# SD1-37_Rev1.net
KiCad netlist of a schematic drawn in EAGLE
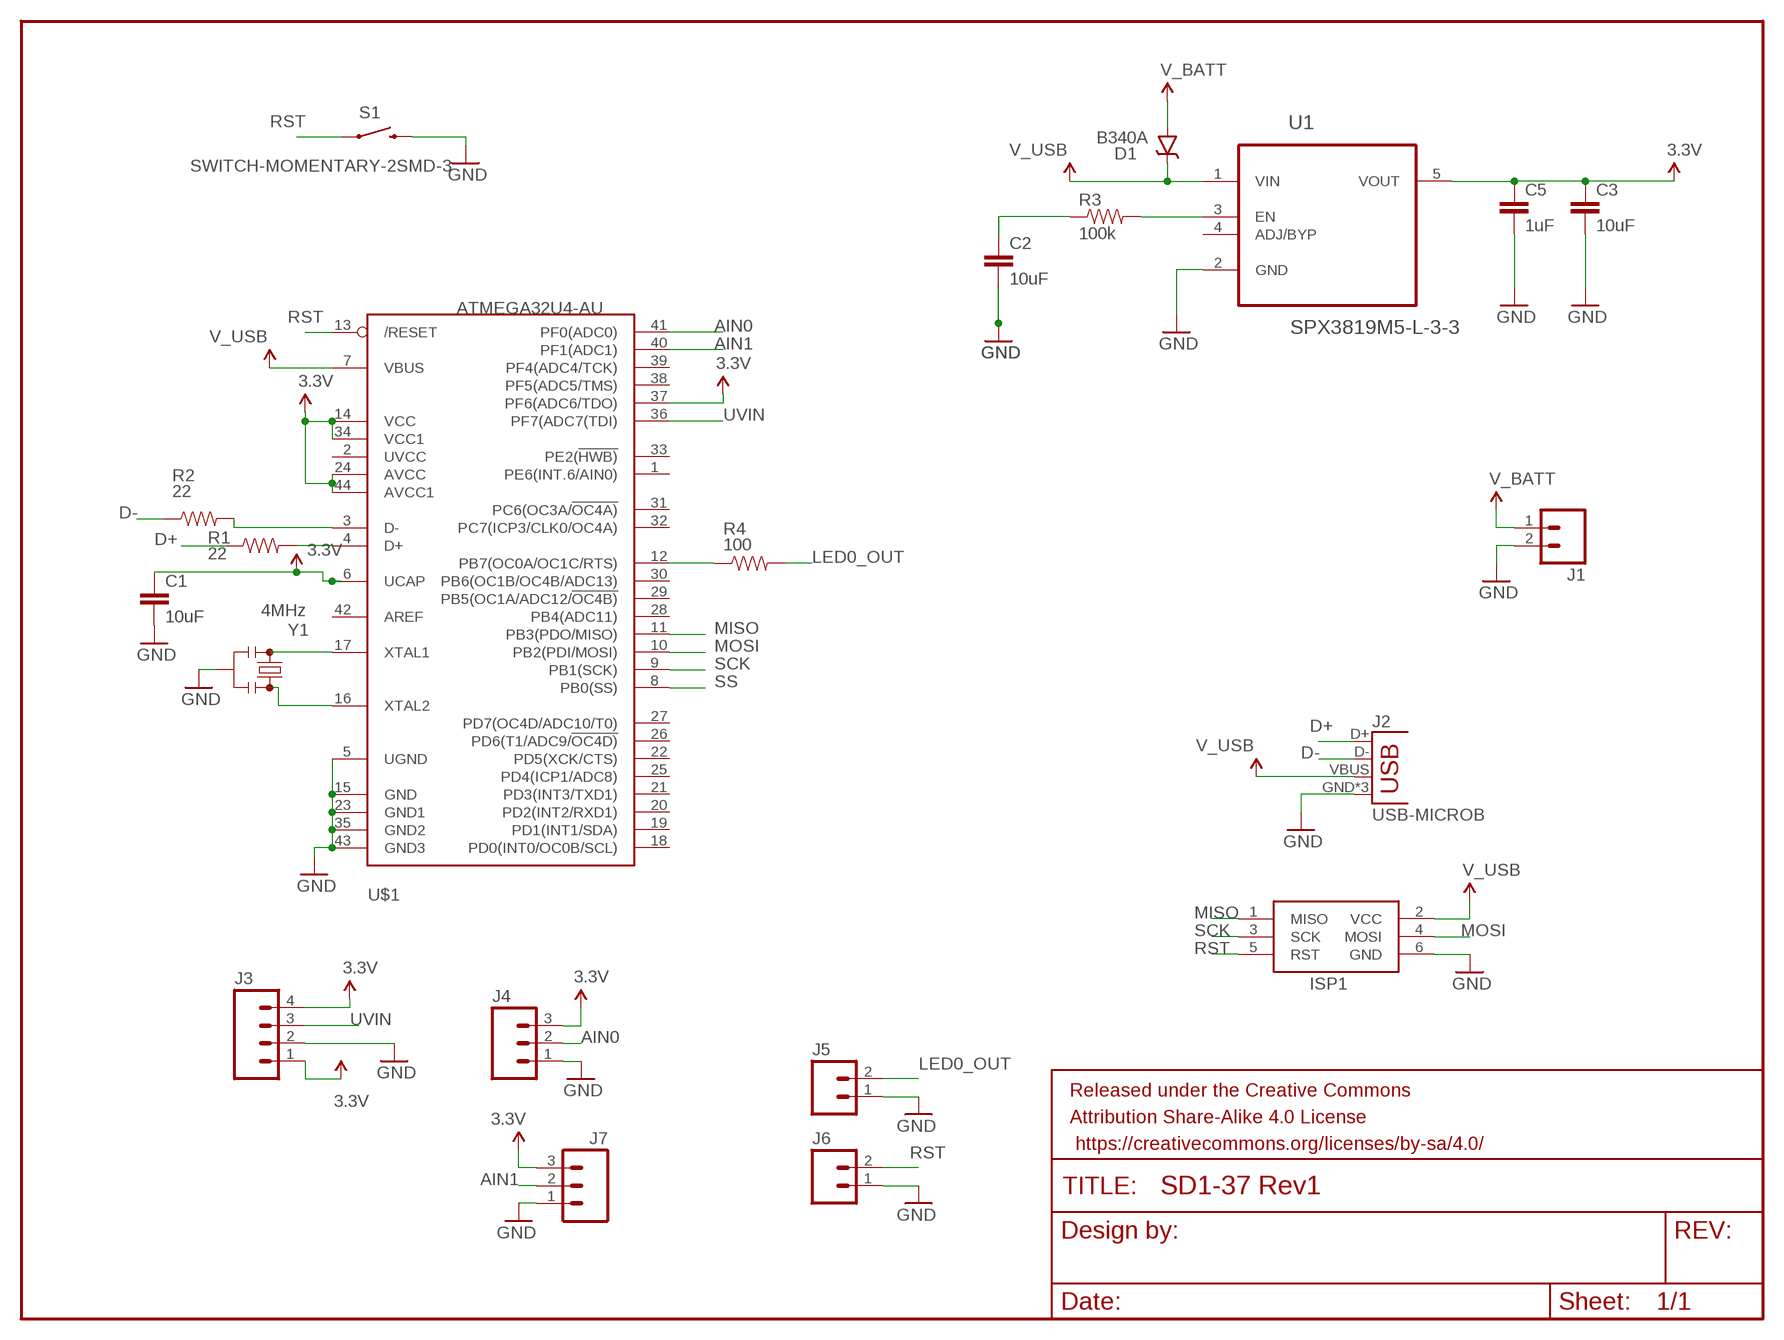
[diagram p0: schematic, sheet 1]

(export (version "E")
  (design (tool "Eeschema 10.0.6"))
  (components
    (comp (ref "C1")
      (value "10uF")
      (footprint "eagle-import:0805")
      (libsource (lib "eagle-import") (part "CAP0805"))
    )
    (comp (ref "C2")
      (value "10uF")
      (footprint "eagle-import:0805")
      (libsource (lib "eagle-import") (part "CAP0805"))
    )
    (comp (ref "C3")
      (value "10uF")
      (footprint "eagle-import:0805")
      (libsource (lib "eagle-import") (part "CAP0805"))
    )
    (comp (ref "C5")
      (value "1uF")
      (footprint "eagle-import:0805")
      (libsource (lib "eagle-import") (part "CAP0805"))
    )
    (comp (ref "D1")
      (value "B340A")
      (footprint "eagle-import:SMA-DIODE")
      (libsource (lib "eagle-import") (part "DIODE-SCHOTTKY-B340A"))
    )
    (comp (ref "FRAME1")
      (value "FRAME-LETTER")
      (footprint "eagle-import:CREATIVE_COMMONS")
      (libsource (lib "eagle-import") (part "FRAME-LETTER"))
    )
    (comp (ref "ISP1")
      (value "AVRISP-6")
      (footprint "eagle-import:AVRISP")
      (libsource (lib "eagle-import") (part "AVRISP-6"))
    )
    (comp (ref "J1")
      (value "M02PTH")
      (footprint "eagle-import:1X02")
      (libsource (lib "eagle-import") (part "M02PTH"))
    )
    (comp (ref "J2")
      (value "USB-MICROB")
      (footprint "eagle-import:USB-MICROB")
      (libsource (lib "eagle-import") (part "USB-MICROB"))
    )
    (comp (ref "J3")
      (value "M04SCREW")
      (footprint "eagle-import:SCREWTERMINAL-3.5MM-4")
      (libsource (lib "eagle-import") (part "M04SCREW"))
    )
    (comp (ref "J4")
      (value "M03SCREW")
      (footprint "eagle-import:SCREWTERMINAL-3.5MM-3")
      (libsource (lib "eagle-import") (part "M03SCREW"))
    )
    (comp (ref "J5")
      (value "M023.5MM")
      (footprint "eagle-import:SCREWTERMINAL-3.5MM-2")
      (libsource (lib "eagle-import") (part "M023.5MM"))
    )
    (comp (ref "J6")
      (value "M023.5MM")
      (footprint "eagle-import:SCREWTERMINAL-3.5MM-2")
      (libsource (lib "eagle-import") (part "M023.5MM"))
    )
    (comp (ref "J7")
      (value "M03SCREW")
      (footprint "eagle-import:SCREWTERMINAL-3.5MM-3")
      (libsource (lib "eagle-import") (part "M03SCREW"))
    )
    (comp (ref "R1")
      (value "22")
      (footprint "eagle-import:0805")
      (libsource (lib "eagle-import") (part "RESISTOR0805-RES"))
    )
    (comp (ref "R2")
      (value "22")
      (footprint "eagle-import:0805")
      (libsource (lib "eagle-import") (part "RESISTOR0805-RES"))
    )
    (comp (ref "R3")
      (value "100k")
      (footprint "eagle-import:0805")
      (libsource (lib "eagle-import") (part "SparkFun-Resistors_RESISTOR0805-RES"))
    )
    (comp (ref "R4")
      (value "100")
      (footprint "eagle-import:0805")
      (libsource (lib "eagle-import") (part "RESISTOR0805-RES"))
    )
    (comp (ref "S1")
      (value "SWITCH-MOMENTARY-2SMD-3")
      (footprint "eagle-import:TACTILE_SWITCH_SMD-3")
      (libsource (lib "eagle-import") (part "SWITCH-MOMENTARY-2SMD-3"))
    )
    (comp (ref "U$1")
      (value "ATMEGA32U4-AU")
      (footprint "eagle-import:TQFP44")
      (libsource (lib "eagle-import") (part "ATMEGA32U4-AU"))
    )
    (comp (ref "U1")
      (value "SPX3819M5-L-3-3")
      (footprint "eagle-import:SOT95P280X145-5N")
      (libsource (lib "eagle-import") (part "SPX3819M5-L-3-3"))
    )
    (comp (ref "Y1")
      (value "4MHz")
      (footprint "eagle-import:RESONATOR-SMD_MED")
      (libsource (lib "eagle-import") (part "RESONATOR4MHZ"))
    )
  )
  (nets
    (net (code "1") (name "/AIN0") (class "Default")
      (node (ref "J4") (pin "2") (pinfunction "2_2") (pintype "passive"))
      (node (ref "U$1") (pin "41") (pinfunction "PF0(ADC0)_41") (pintype "bidirectional"))
    )
    (net (code "2") (name "/AIN1") (class "Default")
      (node (ref "J7") (pin "2") (pinfunction "2_2") (pintype "passive"))
      (node (ref "U$1") (pin "40") (pinfunction "PF1(ADC1)_40") (pintype "bidirectional"))
    )
    (net (code "3") (name "/D+") (class "Default")
      (node (ref "J2") (pin "D+") (pinfunction "D+_D+") (pintype "bidirectional"))
      (node (ref "R1") (pin "1") (pinfunction "1_1") (pintype "passive"))
    )
    (net (code "4") (name "/D-") (class "Default")
      (node (ref "J2") (pin "D-") (pinfunction "D-_D-") (pintype "bidirectional"))
      (node (ref "R2") (pin "1") (pinfunction "1_1") (pintype "passive"))
    )
    (net (code "5") (name "/LED0_OUT") (class "Default")
      (node (ref "J5") (pin "2") (pinfunction "2_2") (pintype "passive"))
      (node (ref "R4") (pin "2") (pinfunction "2_2") (pintype "passive"))
    )
    (net (code "6") (name "/MISO") (class "Default")
      (node (ref "ISP1") (pin "1") (pinfunction "MISO_1") (pintype "input"))
      (node (ref "U$1") (pin "11") (pinfunction "PB3(PDO/MISO)_11") (pintype "bidirectional"))
    )
    (net (code "7") (name "/MOSI") (class "Default")
      (node (ref "ISP1") (pin "4") (pinfunction "MOSI_4") (pintype "output"))
      (node (ref "U$1") (pin "10") (pinfunction "PB2(PDI/MOSI)_10") (pintype "bidirectional"))
    )
    (net (code "8") (name "/RST") (class "Default")
      (node (ref "ISP1") (pin "5") (pinfunction "RST_5") (pintype "output"))
      (node (ref "J6") (pin "2") (pinfunction "2_2") (pintype "passive"))
      (node (ref "S1") (pin "1") (pinfunction "1_1") (pintype "passive"))
      (node (ref "U$1") (pin "13") (pinfunction "/RESET_13") (pintype "bidirectional"))
    )
    (net (code "9") (name "/SCK") (class "Default")
      (node (ref "ISP1") (pin "3") (pinfunction "SCK_3") (pintype "output"))
      (node (ref "U$1") (pin "9") (pinfunction "PB1(SCK)_9") (pintype "bidirectional"))
    )
    (net (code "10") (name "/SS") (class "Default")
      (node (ref "U$1") (pin "8") (pinfunction "PB0(SS)_8") (pintype "bidirectional"))
    )
    (net (code "11") (name "/UVIN") (class "Default")
      (node (ref "J3") (pin "3") (pinfunction "3_3") (pintype "passive"))
      (node (ref "U$1") (pin "36") (pinfunction "PF7(ADC7(TDI)_36") (pintype "bidirectional"))
    )
    (net (code "12") (name "3.3V") (class "Default")
      (node (ref "C1") (pin "1") (pinfunction "1_1") (pintype "passive"))
      (node (ref "C3") (pin "1") (pinfunction "1_1") (pintype "passive"))
      (node (ref "C5") (pin "1") (pinfunction "1_1") (pintype "passive"))
      (node (ref "J3") (pin "1") (pinfunction "1_1") (pintype "passive"))
      (node (ref "J3") (pin "4") (pinfunction "4_4") (pintype "passive"))
      (node (ref "J4") (pin "3") (pinfunction "3_3") (pintype "passive"))
      (node (ref "J7") (pin "3") (pinfunction "3_3") (pintype "passive"))
      (node (ref "U$1") (pin "14") (pinfunction "VCC_14") (pintype "bidirectional"))
      (node (ref "U$1") (pin "24") (pinfunction "AVCC_24") (pintype "bidirectional"))
      (node (ref "U$1") (pin "34") (pinfunction "VCC1_34") (pintype "bidirectional"))
      (node (ref "U$1") (pin "37") (pinfunction "PF6(ADC6/TDO)_37") (pintype "bidirectional"))
      (node (ref "U$1") (pin "44") (pinfunction "AVCC1_44") (pintype "bidirectional"))
      (node (ref "U$1") (pin "6") (pinfunction "UCAP_6") (pintype "bidirectional"))
      (node (ref "U1") (pin "5") (pinfunction "VOUT_5") (pintype "output"))
    )
    (net (code "13") (name "GND") (class "Default")
      (node (ref "C1") (pin "2") (pinfunction "2_2") (pintype "passive"))
      (node (ref "C2") (pin "2") (pinfunction "2_2") (pintype "passive"))
      (node (ref "C3") (pin "2") (pinfunction "2_2") (pintype "passive"))
      (node (ref "C5") (pin "2") (pinfunction "2_2") (pintype "passive"))
      (node (ref "ISP1") (pin "6") (pinfunction "GND_6") (pintype "power_in"))
      (node (ref "J1") (pin "2") (pinfunction "2_2") (pintype "passive"))
      (node (ref "J2") (pin "GND") (pinfunction "GND_GND") (pintype "bidirectional"))
      (node (ref "J2") (pin "MT1") (pinfunction "GND_MT1") (pintype "bidirectional"))
      (node (ref "J2") (pin "MT2") (pinfunction "GND_MT2") (pintype "bidirectional"))
      (node (ref "J3") (pin "2") (pinfunction "2_2") (pintype "passive"))
      (node (ref "J4") (pin "1") (pinfunction "1_1") (pintype "passive"))
      (node (ref "J5") (pin "1") (pinfunction "1_1") (pintype "passive"))
      (node (ref "J6") (pin "1") (pinfunction "1_1") (pintype "passive"))
      (node (ref "J7") (pin "1") (pinfunction "1_1") (pintype "passive"))
      (node (ref "S1") (pin "4") (pinfunction "2_4") (pintype "passive"))
      (node (ref "U$1") (pin "15") (pinfunction "GND_15") (pintype "bidirectional"))
      (node (ref "U$1") (pin "23") (pinfunction "GND1_23") (pintype "bidirectional"))
      (node (ref "U$1") (pin "35") (pinfunction "GND2_35") (pintype "bidirectional"))
      (node (ref "U$1") (pin "43") (pinfunction "GND3_43") (pintype "bidirectional"))
      (node (ref "U$1") (pin "5") (pinfunction "UGND_5") (pintype "bidirectional"))
      (node (ref "U1") (pin "2") (pinfunction "GND_2") (pintype "passive"))
      (node (ref "Y1") (pin "2") (pinfunction "2_2") (pintype "passive"))
    )
    (net (code "14") (name "Net-(C2-Pad1)") (class "Default")
      (node (ref "C2") (pin "1") (pinfunction "1_1") (pintype "passive"))
      (node (ref "R3") (pin "1") (pinfunction "1_1") (pintype "passive"))
    )
    (net (code "15") (name "Net-(U$1-D+)") (class "Default")
      (node (ref "R1") (pin "2") (pinfunction "2_2") (pintype "passive"))
      (node (ref "U$1") (pin "4") (pinfunction "D+_4") (pintype "bidirectional"))
    )
    (net (code "16") (name "Net-(U$1-D-)") (class "Default")
      (node (ref "R2") (pin "2") (pinfunction "2_2") (pintype "passive"))
      (node (ref "U$1") (pin "3") (pinfunction "D-_3") (pintype "bidirectional"))
    )
    (net (code "17") (name "Net-(U$1-PB7(OC0A{slash}OC1C{slash}RTS))") (class "Default")
      (node (ref "R4") (pin "1") (pinfunction "1_1") (pintype "passive"))
      (node (ref "U$1") (pin "12") (pinfunction "PB7(OC0A/OC1C/RTS)_12") (pintype "bidirectional"))
    )
    (net (code "18") (name "Net-(U$1-XTAL1)") (class "Default")
      (node (ref "U$1") (pin "17") (pinfunction "XTAL1_17") (pintype "bidirectional"))
      (node (ref "Y1") (pin "1") (pinfunction "1_1") (pintype "passive"))
    )
    (net (code "19") (name "Net-(U$1-XTAL2)") (class "Default")
      (node (ref "U$1") (pin "16") (pinfunction "XTAL2_16") (pintype "bidirectional"))
      (node (ref "Y1") (pin "3") (pinfunction "3_3") (pintype "passive"))
    )
    (net (code "20") (name "Net-(U1-EN)") (class "Default")
      (node (ref "R3") (pin "2") (pinfunction "2_2") (pintype "passive"))
      (node (ref "U1") (pin "3") (pinfunction "EN_3") (pintype "input"))
    )
    (net (code "21") (name "V_BATT") (class "Default")
      (node (ref "D1") (pin "A") (pinfunction "A_A") (pintype "passive"))
      (node (ref "J1") (pin "1") (pinfunction "1_1") (pintype "passive"))
    )
    (net (code "22") (name "V_USB") (class "Default")
      (node (ref "D1") (pin "C") (pinfunction "C_C") (pintype "passive"))
      (node (ref "ISP1") (pin "2") (pinfunction "VCC_2") (pintype "power_in"))
      (node (ref "J2") (pin "VBUS") (pinfunction "VBUS_VBUS") (pintype "bidirectional"))
      (node (ref "U$1") (pin "7") (pinfunction "VBUS_7") (pintype "bidirectional"))
      (node (ref "U1") (pin "1") (pinfunction "VIN_1") (pintype "power_in"))
    )
    (net (code "23") (name "unconnected-(U$1-AREF-Pad42)") (class "Default")
      (node (ref "U$1") (pin "42") (pinfunction "AREF_42") (pintype "bidirectional"))
    )
    (net (code "24") (name "unconnected-(U$1-PB4(ADC11)-Pad28)") (class "Default")
      (node (ref "U$1") (pin "28") (pinfunction "PB4(ADC11)_28") (pintype "bidirectional"))
    )
    (net (code "25") (name "unconnected-(U$1-PB5(OC1A{slash}ADC12{slash}~{OC4B})-Pad29)") (class "Default")
      (node (ref "U$1") (pin "29") (pinfunction "PB5(OC1A/ADC12/~{OC4B})_29") (pintype "bidirectional"))
    )
    (net (code "26") (name "unconnected-(U$1-PB6(OC1B{slash}OC4B{slash}ADC13)-Pad30)") (class "Default")
      (node (ref "U$1") (pin "30") (pinfunction "PB6(OC1B/OC4B/ADC13)_30") (pintype "bidirectional"))
    )
    (net (code "27") (name "unconnected-(U$1-PC6(OC3A{slash}~{OC4A})-Pad31)") (class "Default")
      (node (ref "U$1") (pin "31") (pinfunction "PC6(OC3A/~{OC4A})_31") (pintype "bidirectional"))
    )
    (net (code "28") (name "unconnected-(U$1-PC7(ICP3{slash}CLK0{slash}OC4A)-Pad32)") (class "Default")
      (node (ref "U$1") (pin "32") (pinfunction "PC7(ICP3/CLK0/OC4A)_32") (pintype "bidirectional"))
    )
    (net (code "29") (name "unconnected-(U$1-PD0(INT0{slash}OC0B{slash}SCL)-Pad18)") (class "Default")
      (node (ref "U$1") (pin "18") (pinfunction "PD0(INT0/OC0B/SCL)_18") (pintype "bidirectional"))
    )
    (net (code "30") (name "unconnected-(U$1-PD1(INT1{slash}SDA)-Pad19)") (class "Default")
      (node (ref "U$1") (pin "19") (pinfunction "PD1(INT1/SDA)_19") (pintype "bidirectional"))
    )
    (net (code "31") (name "unconnected-(U$1-PD2(INT2{slash}RXD1)-Pad20)") (class "Default")
      (node (ref "U$1") (pin "20") (pinfunction "PD2(INT2/RXD1)_20") (pintype "bidirectional"))
    )
    (net (code "32") (name "unconnected-(U$1-PD3(INT3{slash}TXD1)-Pad21)") (class "Default")
      (node (ref "U$1") (pin "21") (pinfunction "PD3(INT3/TXD1)_21") (pintype "bidirectional"))
    )
    (net (code "33") (name "unconnected-(U$1-PD4(ICP1{slash}ADC8)-Pad25)") (class "Default")
      (node (ref "U$1") (pin "25") (pinfunction "PD4(ICP1/ADC8)_25") (pintype "bidirectional"))
    )
    (net (code "34") (name "unconnected-(U$1-PD5(XCK{slash}CTS)-Pad22)") (class "Default")
      (node (ref "U$1") (pin "22") (pinfunction "PD5(XCK/CTS)_22") (pintype "bidirectional"))
    )
    (net (code "35") (name "unconnected-(U$1-PD6(T1{slash}ADC9{slash}~{OC4D})-Pad26)") (class "Default")
      (node (ref "U$1") (pin "26") (pinfunction "PD6(T1/ADC9/~{OC4D})_26") (pintype "bidirectional"))
    )
    (net (code "36") (name "unconnected-(U$1-PD7(OC4D{slash}ADC10{slash}T0)-Pad27)") (class "Default")
      (node (ref "U$1") (pin "27") (pinfunction "PD7(OC4D/ADC10/T0)_27") (pintype "bidirectional"))
    )
    (net (code "37") (name "unconnected-(U$1-PE2(~{HWB})-Pad33)") (class "Default")
      (node (ref "U$1") (pin "33") (pinfunction "PE2(~{HWB})_33") (pintype "bidirectional"))
    )
    (net (code "38") (name "unconnected-(U$1-PE6(INT.6{slash}AIN0)-Pad1)") (class "Default")
      (node (ref "U$1") (pin "1") (pinfunction "PE6(INT.6/AIN0)_1") (pintype "bidirectional"))
    )
    (net (code "39") (name "unconnected-(U$1-PF4(ADC4{slash}TCK)-Pad39)") (class "Default")
      (node (ref "U$1") (pin "39") (pinfunction "PF4(ADC4/TCK)_39") (pintype "bidirectional"))
    )
    (net (code "40") (name "unconnected-(U$1-PF5(ADC5{slash}TMS)-Pad38)") (class "Default")
      (node (ref "U$1") (pin "38") (pinfunction "PF5(ADC5/TMS)_38") (pintype "bidirectional"))
    )
    (net (code "41") (name "unconnected-(U$1-UVCC-Pad2)") (class "Default")
      (node (ref "U$1") (pin "2") (pinfunction "UVCC_2") (pintype "bidirectional"))
    )
    (net (code "42") (name "unconnected-(U1-ADJ{slash}BYP-Pad4)") (class "Default")
      (node (ref "U1") (pin "4") (pinfunction "ADJ/BYP_4") (pintype "passive"))
    )
  )
)
